# HashPower4.net
KiCad netlist of a schematic drawn in Altium Designer
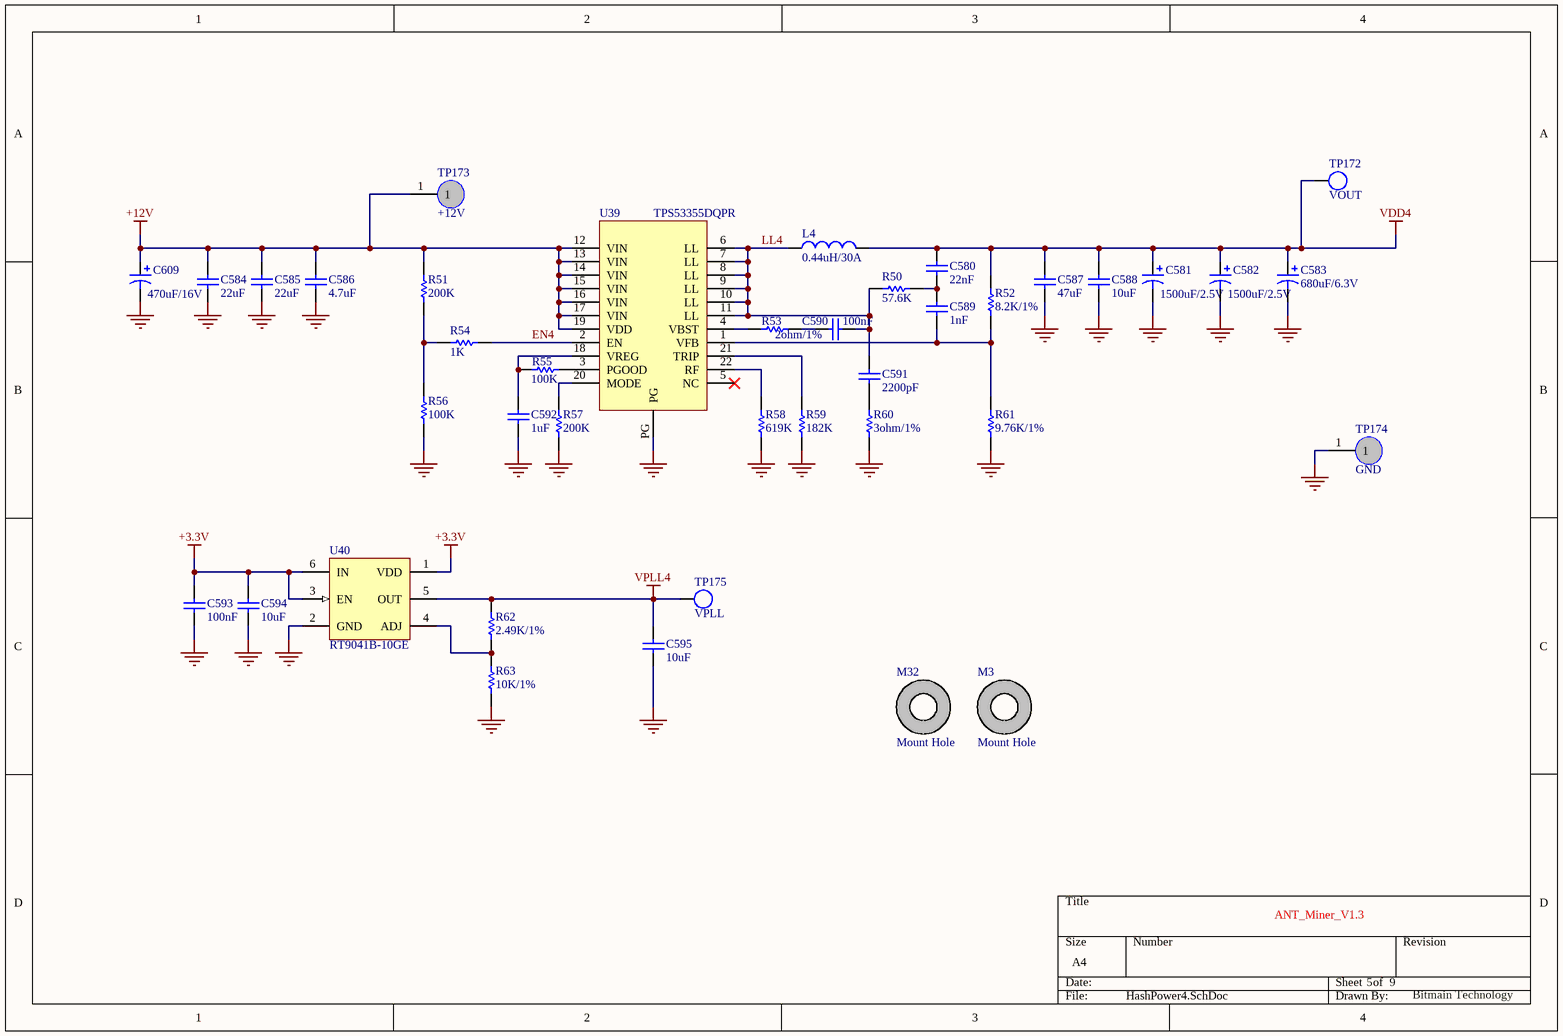
[diagram p0: HashPower4.SchDoc]

(export (version "E")
  (design (tool "Eeschema 10.0.6"))
  (components
    (comp (ref "C580")
      (value "22nF")
      (footprint "CC0603(1608)")
      (description "Capacitor")
      (libsource (lib "ANT_Miner_V1.3") (part "Cap"))
    )
    (comp (ref "C581")
      (value "1500uF/2.5V")
      (footprint "F12")
      (description "Polarized Capacitor (SMD)")
      (fields (field (name "Comment") "1500uF/4V"))
      (libsource (lib "ANT_Miner_V1.3") (part "Cap Pol2"))
    )
    (comp (ref "C582")
      (value "1500uF/2.5V")
      (footprint "F12")
      (description "Polarized Capacitor (SMD)")
      (fields (field (name "Comment") "1500uF/4V"))
      (libsource (lib "ANT_Miner_V1.3") (part "Cap Pol2"))
    )
    (comp (ref "C583")
      (value "680uF/6.3V")
      (footprint "D")
      (description "Polarized Capacitor (Surface Mount)")
      (fields (field (name "PUBLISHER") "Altium Limited"))
      (libsource (lib "Miscellaneous Devices") (part "Cap Pol3"))
    )
    (comp (ref "C584")
      (value "22uF")
      (footprint "CC1210(3225)")
      (description "Capacitor")
      (libsource (lib "ANT_Miner_V1.3") (part "Cap"))
    )
    (comp (ref "C585")
      (value "22uF")
      (footprint "CC1210(3225)")
      (description "Capacitor")
      (libsource (lib "ANT_Miner_V1.3") (part "Cap"))
    )
    (comp (ref "C586")
      (value "4.7uF")
      (footprint "CC0805(2012)")
      (description "Capacitor")
      (libsource (lib "ANT_Miner_V1.3") (part "Cap"))
    )
    (comp (ref "C587")
      (value "47uF")
      (footprint "CAPC3225L")
      (description "Capacitor (Semiconductor SIM Model)")
      (fields (field (name "PUBLISHER") "Altium Limited"))
      (libsource (lib "Miscellaneous Devices") (part "Cap Semi"))
    )
    (comp (ref "C588")
      (value "10uF")
      (footprint "CAPC2012L")
      (description "Capacitor (Semiconductor SIM Model)")
      (fields (field (name "PUBLISHER") "Altium Limited"))
      (libsource (lib "Miscellaneous Devices") (part "Cap Semi"))
    )
    (comp (ref "C589")
      (value "1nF")
      (footprint "CC0603(1608)")
      (description "Capacitor")
      (libsource (lib "ANT_Miner_V1.3") (part "Cap"))
    )
    (comp (ref "C590")
      (value "100nF")
      (footprint "CC0603(1608)")
      (description "Capacitor")
      (libsource (lib "ANT_Miner_V1.3") (part "Cap"))
    )
    (comp (ref "C591")
      (value "2200pF")
      (footprint "CC0603(1608)")
      (description "Capacitor")
      (libsource (lib "ANT_Miner_V1.3") (part "Cap"))
    )
    (comp (ref "C592")
      (value "1uF")
      (footprint "CC0603(1608)")
      (description "Capacitor")
      (libsource (lib "ANT_Miner_V1.3") (part "Cap"))
    )
    (comp (ref "C593")
      (value "100nF")
      (footprint "CC0603(1608)")
      (description "Capacitor (Semiconductor SIM Model)")
      (fields (field (name "PUBLISHER") "Altium Limited"))
      (libsource (lib "CtrlUnit_10U_V1.0") (part "Cap Semi"))
    )
    (comp (ref "C594")
      (value "10uF")
      (footprint "CC0805(2012)")
      (description "Capacitor (Semiconductor SIM Model)")
      (fields (field (name "PUBLISHER") "Altium Limited"))
      (libsource (lib "CtrlUnit_10U_V1.0") (part "Cap Semi"))
    )
    (comp (ref "C595")
      (value "10uF")
      (footprint "CC0805(2012)")
      (description "Capacitor (Semiconductor SIM Model)")
      (fields (field (name "PUBLISHER") "Altium Limited"))
      (libsource (lib "CtrlUnit_10U_V1.0") (part "Cap Semi"))
    )
    (comp (ref "C609")
      (value "470uF/16V")
      (footprint "E12")
      (description "Polarized Capacitor (SMD)")
      (libsource (lib "ANT_Miner_V1.3") (part "Cap Pol2"))
    )
    (comp (ref "L4")
      (value "0.44uH/30A")
      (footprint "IHLP5050")
      (description "Inductor")
      (fields (field (name "PUBLISHER") "Altium Limited"))
      (libsource (lib "Miscellaneous Devices") (part "Inductor"))
    )
    (comp (ref "M3") (value "Mount Hole") (footprint "HOLE_3.2") (libsource (lib "S6_2") (part "M_Hole")))
    (comp (ref "M32") (value "Mount Hole") (footprint "HOLE_3.2") (libsource (lib "S6_2") (part "M_Hole")))
    (comp (ref "R50")
      (value "57.6K")
      (footprint "RR0603(1608)")
      (description "Resistor")
      (libsource (lib "ANT_Miner_V1.3") (part "Res1"))
    )
    (comp (ref "R51")
      (value "200K")
      (footprint "RR0603(1608)")
      (description "Resistor")
      (libsource (lib "ANT_Miner_V1.3") (part "Res1"))
    )
    (comp (ref "R52")
      (value "8.2K/1%")
      (footprint "RR0603(1608)")
      (description "Resistor")
      (libsource (lib "ANT_Miner_V1.3") (part "Res1"))
    )
    (comp (ref "R53")
      (value "2ohm/1%")
      (footprint "RR0603(1608)")
      (description "Resistor")
      (fields (field (name "Comment") "2"))
      (libsource (lib "ANT_Miner_V1.3") (part "Res1"))
    )
    (comp (ref "R54")
      (value "1K")
      (footprint "RR0603(1608)")
      (description "Resistor")
      (libsource (lib "ANT_Miner_V1.3") (part "Res1"))
    )
    (comp (ref "R55")
      (value "100K")
      (footprint "RR0603(1608)")
      (description "Resistor")
      (libsource (lib "ANT_Miner_V1.3") (part "Res1"))
    )
    (comp (ref "R56")
      (value "100K")
      (footprint "RR0603(1608)")
      (description "Resistor")
      (libsource (lib "ANT_Miner_V1.3") (part "Res1"))
    )
    (comp (ref "R57")
      (value "200K")
      (footprint "RR0603(1608)")
      (description "Resistor")
      (libsource (lib "ANT_Miner_V1.3") (part "Res1"))
    )
    (comp (ref "R58")
      (value "619K")
      (footprint "RR0603(1608)")
      (description "Resistor")
      (libsource (lib "ANT_Miner_V1.3") (part "Res1"))
    )
    (comp (ref "R59")
      (value "182K")
      (footprint "RR0603(1608)")
      (description "Resistor")
      (libsource (lib "ANT_Miner_V1.3") (part "Res1"))
    )
    (comp (ref "R60")
      (value "3ohm/1%")
      (footprint "RR0603(1608)")
      (description "Resistor")
      (fields (field (name "Comment") "3"))
      (libsource (lib "ANT_Miner_V1.3") (part "Res1"))
    )
    (comp (ref "R61")
      (value "9.76K/1%")
      (footprint "RR0603(1608)")
      (description "Resistor")
      (libsource (lib "ANT_Miner_V1.3") (part "Res1"))
    )
    (comp (ref "R62")
      (value "2.49K/1%")
      (footprint "RR0603(1608)")
      (description "Resistor")
      (fields (field (name "PUBLISHER") "Altium Limited"))
      (libsource (lib "CtrlUnit_10U_V1.0") (part "Res1"))
    )
    (comp (ref "R63")
      (value "10K/1%")
      (footprint "RR0603(1608)")
      (description "Resistor")
      (fields (field (name "PUBLISHER") "Altium Limited"))
      (libsource (lib "CtrlUnit_10U_V1.0") (part "Res1"))
    )
    (comp (ref "TP172")
      (value "VOUT")
      (footprint "TP_SMD_1.0")
      (description "Test Point")
      (libsource (lib "BitMain_Miner_1") (part "TP"))
    )
    (comp (ref "TP173") (value "+12V") (footprint "TP") (libsource (lib "ANT_Miner_V1.3") (part "TP")))
    (comp (ref "TP174") (value "GND") (footprint "TP") (libsource (lib "ANT_Miner_V1.3") (part "TP")))
    (comp (ref "TP175")
      (value "VPLL")
      (footprint "TP_SMD_1.0")
      (description "Test Point")
      (libsource (lib "BitMain_Miner_1") (part "TP"))
    )
    (comp (ref "U39")
      (value "TPS53355DQPR")
      (footprint "TPS53355")
      (libsource (lib "ANT_Miner_V1.3") (part "TPS53355"))
    )
    (comp (ref "U40")
      (value "RT9041B-10GE")
      (footprint "SOT23-6_L")
      (libsource (lib "USB_Miner") (part "RT9041B-10GE"))
    )
  )
  (nets
    (net (code "1") (name "+3.3V") (class "Default")
      (node (ref "C593") (pin "2") (pinfunction "2_2") (pintype "passive"))
      (node (ref "C594") (pin "2") (pinfunction "2_2") (pintype "passive"))
      (node (ref "U40") (pin "1") (pinfunction "VDD_1") (pintype "power_in"))
      (node (ref "U40") (pin "3") (pinfunction "EN_3") (pintype "input"))
      (node (ref "U40") (pin "6") (pinfunction "IN_6") (pintype "power_in"))
    )
    (net (code "2") (name "+12V") (class "Default")
      (node (ref "C584") (pin "1") (pinfunction "1_1") (pintype "passive"))
      (node (ref "C585") (pin "1") (pinfunction "1_1") (pintype "passive"))
      (node (ref "C586") (pin "1") (pinfunction "1_1") (pintype "passive"))
      (node (ref "C609") (pin "1") (pinfunction "1_1") (pintype "passive"))
      (node (ref "R51") (pin "1") (pinfunction "1_1") (pintype "passive"))
      (node (ref "TP173") (pin "1") (pinfunction "1_1") (pintype "passive"))
      (node (ref "U39") (pin "12") (pinfunction "VIN_12") (pintype "passive"))
      (node (ref "U39") (pin "13") (pinfunction "VIN_13") (pintype "passive"))
      (node (ref "U39") (pin "14") (pinfunction "VIN_14") (pintype "passive"))
      (node (ref "U39") (pin "15") (pinfunction "VIN_15") (pintype "passive"))
      (node (ref "U39") (pin "16") (pinfunction "VIN_16") (pintype "passive"))
      (node (ref "U39") (pin "17") (pinfunction "VIN_17") (pintype "passive"))
      (node (ref "U39") (pin "19") (pinfunction "VDD_19") (pintype "passive"))
    )
    (net (code "3") (name "/EN4") (class "Default")
      (node (ref "R54") (pin "2") (pinfunction "2_2") (pintype "passive"))
      (node (ref "U39") (pin "2") (pinfunction "EN_2") (pintype "passive"))
    )
    (net (code "4") (name "/LL4") (class "Default")
      (node (ref "C590") (pin "2") (pinfunction "2_2") (pintype "passive"))
      (node (ref "C591") (pin "1") (pinfunction "1_1") (pintype "passive"))
      (node (ref "L4") (pin "1") (pinfunction "1_1") (pintype "passive"))
      (node (ref "R50") (pin "1") (pinfunction "1_1") (pintype "passive"))
      (node (ref "U39") (pin "10") (pinfunction "LL_10") (pintype "passive"))
      (node (ref "U39") (pin "11") (pinfunction "LL_11") (pintype "passive"))
      (node (ref "U39") (pin "6") (pinfunction "LL_6") (pintype "passive"))
      (node (ref "U39") (pin "7") (pinfunction "LL_7") (pintype "passive"))
      (node (ref "U39") (pin "8") (pinfunction "LL_8") (pintype "passive"))
      (node (ref "U39") (pin "9") (pinfunction "LL_9") (pintype "passive"))
    )
    (net (code "5") (name "GND") (class "Default")
      (node (ref "C581") (pin "2") (pinfunction "2_2") (pintype "passive"))
      (node (ref "C582") (pin "2") (pinfunction "2_2") (pintype "passive"))
      (node (ref "C583") (pin "2") (pinfunction "2_2") (pintype "passive"))
      (node (ref "C584") (pin "2") (pinfunction "2_2") (pintype "passive"))
      (node (ref "C585") (pin "2") (pinfunction "2_2") (pintype "passive"))
      (node (ref "C586") (pin "2") (pinfunction "2_2") (pintype "passive"))
      (node (ref "C587") (pin "1") (pinfunction "1_1") (pintype "passive"))
      (node (ref "C588") (pin "1") (pinfunction "1_1") (pintype "passive"))
      (node (ref "C592") (pin "2") (pinfunction "2_2") (pintype "passive"))
      (node (ref "C593") (pin "1") (pinfunction "1_1") (pintype "passive"))
      (node (ref "C594") (pin "1") (pinfunction "1_1") (pintype "passive"))
      (node (ref "C595") (pin "1") (pinfunction "1_1") (pintype "passive"))
      (node (ref "C609") (pin "2") (pinfunction "2_2") (pintype "passive"))
      (node (ref "R56") (pin "2") (pinfunction "2_2") (pintype "passive"))
      (node (ref "R57") (pin "2") (pinfunction "2_2") (pintype "passive"))
      (node (ref "R58") (pin "2") (pinfunction "2_2") (pintype "passive"))
      (node (ref "R59") (pin "2") (pinfunction "2_2") (pintype "passive"))
      (node (ref "R60") (pin "2") (pinfunction "2_2") (pintype "passive"))
      (node (ref "R61") (pin "2") (pinfunction "2_2") (pintype "passive"))
      (node (ref "R63") (pin "1") (pinfunction "1_1") (pintype "passive"))
      (node (ref "TP174") (pin "1") (pinfunction "1_1") (pintype "passive"))
      (node (ref "U39") (pin "PG") (pinfunction "PG_PG") (pintype "passive"))
      (node (ref "U40") (pin "2") (pinfunction "GND_2") (pintype "power_in"))
    )
    (net (code "6") (name "Net-(C580-Pad2)") (class "Default")
      (node (ref "C580") (pin "2") (pinfunction "2_2") (pintype "passive"))
      (node (ref "C589") (pin "1") (pinfunction "1_1") (pintype "passive"))
      (node (ref "R50") (pin "2") (pinfunction "2_2") (pintype "passive"))
    )
    (net (code "7") (name "Net-(C590-Pad1)") (class "Default")
      (node (ref "C590") (pin "1") (pinfunction "1_1") (pintype "passive"))
      (node (ref "R53") (pin "2") (pinfunction "2_2") (pintype "passive"))
    )
    (net (code "8") (name "Net-(C591-Pad2)") (class "Default")
      (node (ref "C591") (pin "2") (pinfunction "2_2") (pintype "passive"))
      (node (ref "R60") (pin "1") (pinfunction "1_1") (pintype "passive"))
    )
    (net (code "9") (name "Net-(R51-Pad2)") (class "Default")
      (node (ref "R51") (pin "2") (pinfunction "2_2") (pintype "passive"))
      (node (ref "R54") (pin "1") (pinfunction "1_1") (pintype "passive"))
      (node (ref "R56") (pin "1") (pinfunction "1_1") (pintype "passive"))
    )
    (net (code "10") (name "Net-(U39-MODE)") (class "Default")
      (node (ref "R57") (pin "1") (pinfunction "1_1") (pintype "passive"))
      (node (ref "U39") (pin "20") (pinfunction "MODE_20") (pintype "passive"))
    )
    (net (code "11") (name "Net-(U39-PGOOD)") (class "Default")
      (node (ref "R55") (pin "2") (pinfunction "2_2") (pintype "passive"))
      (node (ref "U39") (pin "3") (pinfunction "PGOOD_3") (pintype "passive"))
    )
    (net (code "12") (name "Net-(U39-RF)") (class "Default")
      (node (ref "R58") (pin "1") (pinfunction "1_1") (pintype "passive"))
      (node (ref "U39") (pin "22") (pinfunction "RF_22") (pintype "passive"))
    )
    (net (code "13") (name "Net-(U39-TRIP)") (class "Default")
      (node (ref "R59") (pin "1") (pinfunction "1_1") (pintype "passive"))
      (node (ref "U39") (pin "21") (pinfunction "TRIP_21") (pintype "passive"))
    )
    (net (code "14") (name "Net-(U39-VBST)") (class "Default")
      (node (ref "R53") (pin "1") (pinfunction "1_1") (pintype "passive"))
      (node (ref "U39") (pin "4") (pinfunction "VBST_4") (pintype "passive"))
    )
    (net (code "15") (name "Net-(U39-VFB)") (class "Default")
      (node (ref "C589") (pin "2") (pinfunction "2_2") (pintype "passive"))
      (node (ref "R52") (pin "2") (pinfunction "2_2") (pintype "passive"))
      (node (ref "R61") (pin "1") (pinfunction "1_1") (pintype "passive"))
      (node (ref "U39") (pin "1") (pinfunction "VFB_1") (pintype "passive"))
    )
    (net (code "16") (name "Net-(U39-VREG)") (class "Default")
      (node (ref "C592") (pin "1") (pinfunction "1_1") (pintype "passive"))
      (node (ref "R55") (pin "1") (pinfunction "1_1") (pintype "passive"))
      (node (ref "U39") (pin "18") (pinfunction "VREG_18") (pintype "passive"))
    )
    (net (code "17") (name "Net-(U40-ADJ)") (class "Default")
      (node (ref "R62") (pin "1") (pinfunction "1_1") (pintype "passive"))
      (node (ref "R63") (pin "2") (pinfunction "2_2") (pintype "passive"))
      (node (ref "U40") (pin "4") (pinfunction "ADJ_4") (pintype "passive"))
    )
    (net (code "18") (name "VDD4") (class "Default")
      (node (ref "C580") (pin "1") (pinfunction "1_1") (pintype "passive"))
      (node (ref "C581") (pin "1") (pinfunction "1_1") (pintype "passive"))
      (node (ref "C582") (pin "1") (pinfunction "1_1") (pintype "passive"))
      (node (ref "C583") (pin "1") (pinfunction "1_1") (pintype "passive"))
      (node (ref "C587") (pin "2") (pinfunction "2_2") (pintype "passive"))
      (node (ref "C588") (pin "2") (pinfunction "2_2") (pintype "passive"))
      (node (ref "L4") (pin "2") (pinfunction "2_2") (pintype "passive"))
      (node (ref "R52") (pin "1") (pinfunction "1_1") (pintype "passive"))
      (node (ref "TP172") (pin "1") (pinfunction "1_1") (pintype "passive"))
    )
    (net (code "19") (name "VPLL4") (class "Default")
      (node (ref "C595") (pin "2") (pinfunction "2_2") (pintype "passive"))
      (node (ref "R62") (pin "2") (pinfunction "2_2") (pintype "passive"))
      (node (ref "TP175") (pin "1") (pinfunction "1_1") (pintype "passive"))
      (node (ref "U40") (pin "5") (pinfunction "OUT_5") (pintype "power_in"))
    )
    (net (code "20") (name "unconnected-(M3-PIN-Pad0)") (class "Default")
      (node (ref "M3") (pin "0") (pinfunction "PIN_0") (pintype "power_in"))
    )
    (net (code "21") (name "unconnected-(M32-PIN-Pad0)") (class "Default")
      (node (ref "M32") (pin "0") (pinfunction "PIN_0") (pintype "power_in"))
    )
    (net (code "22") (name "unconnected-(U39-NC-Pad5)") (class "Default")
      (node (ref "U39") (pin "5") (pinfunction "NC_5") (pintype "passive+no_connect"))
    )
  )
)
